# Power.net
KiCad netlist of a schematic drawn in Altium Designer
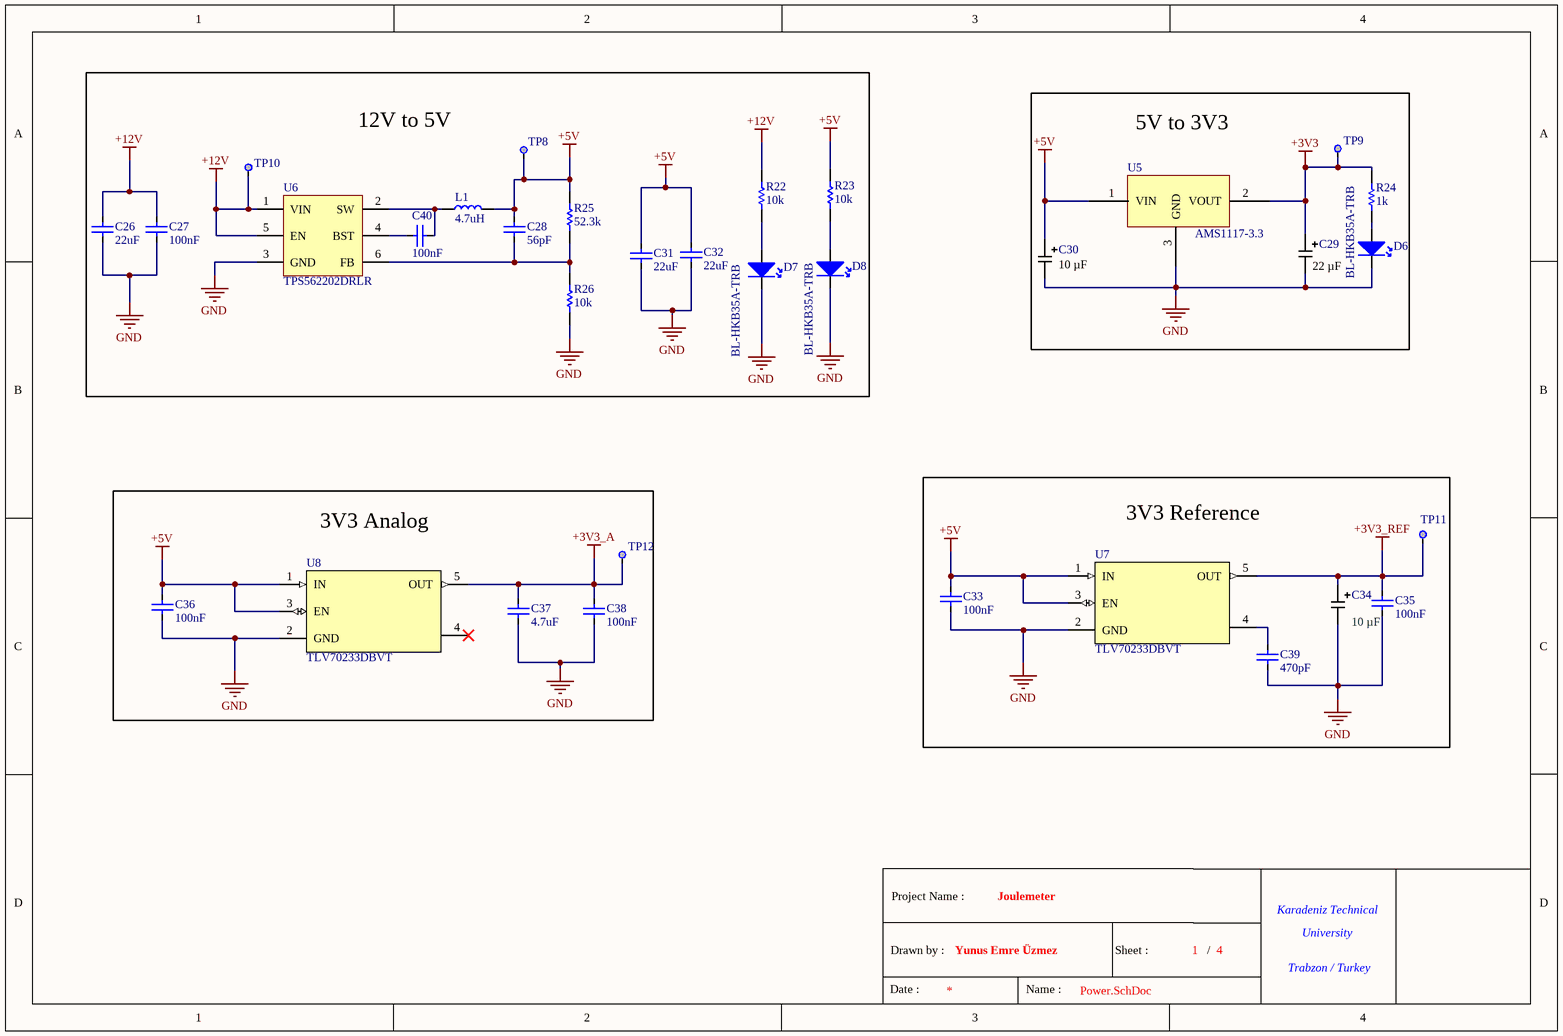
[diagram p0: Power.SchDoc]

(export (version "E")
  (design (tool "Eeschema 10.0.6"))
  (components
    (comp (ref "C26")
      (value "22uF")
      (footprint "CAP-1210")
      (fields
        (field (name "MANUFACTURER") "Samsung Electro-Mechanics")
        (field (name "VOLTAGE") "25V")
        (field (name "TOLERANCE") "%10")
      )
      (libsource (lib "Motor_Driver") (part "CL32B226KAJNNNE"))
    )
    (comp (ref "C27")
      (value "100nF")
      (footprint "CAP-0603")
      (fields
        (field (name "MANUFACTURER") "TDK")
        (field (name "VOLTAGE") "50V")
        (field (name "TOLERANCE") "%10")
      )
      (libsource (lib "Motor_Driver") (part "CGA3E2X7R1H104K080AA"))
    )
    (comp (ref "C28")
      (value "56pF")
      (footprint "Motor_Driver:CAP-0603")
      (fields
        (field (name "MANUFACTURER") "Murata")
        (field (name "TOLERANCE") "%1")
        (field (name "VOLTAGE") "100V")
      )
      (libsource (lib "My_Libs") (part "GCM1885C2A560FA16D"))
    )
    (comp (ref "C29")
      (value "T491B226K020AT")
      (footprint "KEMET_CAP_TAN-B")
      (description "CAP TANT 22UF 10% 20V 1411")
      (fields
        (field (name "MANUFACTURER") "KEMET")
        (field (name "TOLERANCE") "±10%")
        (field (name "CAPACITANCE") "22 µF")
      )
      (libsource (lib "Tantalum Capacitors") (part "T491B226K020AT"))
    )
    (comp (ref "C30")
      (value "T491B106M016AT")
      (footprint "KEMET_CAP_TAN-B")
      (description "CAP TANT 10UF 20% 16V 1411")
      (fields
        (field (name "MANUFACTURER") "KEMET")
        (field (name "TOLERANCE") "±20%")
        (field (name "CAPACITANCE") "10 µF")
      )
      (libsource (lib "Tantalum Capacitors") (part "T491B106M016AT"))
    )
    (comp (ref "C31")
      (value "22uF")
      (footprint "CAP-1210")
      (fields
        (field (name "MANUFACTURER") "Samsung Electro-Mechanics")
        (field (name "VOLTAGE") "25V")
        (field (name "TOLERANCE") "%10")
      )
      (libsource (lib "Motor_Driver") (part "CL32B226KAJNNNE"))
    )
    (comp (ref "C32")
      (value "22uF")
      (footprint "CAP-1210")
      (fields
        (field (name "MANUFACTURER") "Samsung Electro-Mechanics")
        (field (name "VOLTAGE") "25V")
        (field (name "TOLERANCE") "%10")
      )
      (libsource (lib "Motor_Driver") (part "CL32B226KAJNNNE"))
    )
    (comp (ref "C33")
      (value "100nF")
      (footprint "CAP-0603")
      (fields
        (field (name "MANUFACTURER") "TDK")
        (field (name "VOLTAGE") "50V")
        (field (name "TOLERANCE") "%10")
      )
      (libsource (lib "Motor_Driver") (part "CGA3E2X7R1H104K080AA"))
    )
    (comp (ref "C34")
      (value "T491B106M016AT")
      (footprint "KEMET_CAP_TAN-B")
      (description "CAP TANT 10UF 20% 16V 1411")
      (fields
        (field (name "MANUFACTURER") "KEMET")
        (field (name "TOLERANCE") "±20%")
        (field (name "CAPACITANCE") "10 µF")
      )
      (libsource (lib "Tantalum Capacitors") (part "T491B106M016AT"))
    )
    (comp (ref "C35")
      (value "100nF")
      (footprint "CAP-0603")
      (fields
        (field (name "MANUFACTURER") "TDK")
        (field (name "VOLTAGE") "50V")
        (field (name "TOLERANCE") "%10")
      )
      (libsource (lib "Motor_Driver") (part "CGA3E2X7R1H104K080AA"))
    )
    (comp (ref "C36")
      (value "100nF")
      (footprint "CAP-0603")
      (fields
        (field (name "MANUFACTURER") "TDK")
        (field (name "VOLTAGE") "50V")
        (field (name "TOLERANCE") "%10")
      )
      (libsource (lib "Motor_Driver") (part "CGA3E2X7R1H104K080AA"))
    )
    (comp (ref "C37")
      (value "4.7uF")
      (footprint "CAP-0805")
      (fields
        (field (name "MANUFACTURER") "Kemet")
        (field (name "VOLTAGE") "25V")
        (field (name "TOLERANCE") "%10")
      )
      (libsource (lib "Motor_Driver") (part "C0805C475K3RACAUTO"))
    )
    (comp (ref "C38")
      (value "100nF")
      (footprint "CAP-0603")
      (fields
        (field (name "MANUFACTURER") "TDK")
        (field (name "VOLTAGE") "50V")
        (field (name "TOLERANCE") "%10")
      )
      (libsource (lib "Motor_Driver") (part "CGA3E2X7R1H104K080AA"))
    )
    (comp (ref "C39")
      (value "470pF")
      (footprint "CAP-0603")
      (fields
        (field (name "VOLTAGE") "50V")
        (field (name "TOLERANCE") "%10")
        (field (name "MANUFACTURER") "Samsung")
      )
      (libsource (lib "jl_lib") (part "CL10B471KB8NNNC"))
    )
    (comp (ref "C40")
      (value "100nF")
      (footprint "Motor_Driver:CAP-0603")
      (fields
        (field (name "MANUFACTURER") "TDK")
        (field (name "VOLTAGE") "50V")
        (field (name "TOLERANCE") "%10")
      )
      (libsource (lib "My_Libs") (part "CGA3E2X7R1H104K080AA"))
    )
    (comp (ref "D6")
      (value "BL-HKB35A-TRB")
      (footprint "LED-0805")
      (fields (field (name "MANUFACTURER") "BRIGHT LED"))
      (libsource (lib "Motor_Driver") (part "BL-HKB35A-TRB"))
    )
    (comp (ref "D7")
      (value "BL-HKB35A-TRB")
      (footprint "LED-0805")
      (fields (field (name "MANUFACTURER") "BRIGHT LED"))
      (libsource (lib "Motor_Driver") (part "BL-HKB35A-TRB"))
    )
    (comp (ref "D8")
      (value "BL-HKB35A-TRB")
      (footprint "LED-0805")
      (fields (field (name "MANUFACTURER") "BRIGHT LED"))
      (libsource (lib "Motor_Driver") (part "BL-HKB35A-TRB"))
    )
    (comp (ref "L1")
      (value "4.7uH")
      (footprint "Motor_Driver:IND_EATON_DR125-4R7-R")
      (fields (field (name "MANUFACTURER") "Eaton") (field (name "TOLERANCE") "%20"))
      (libsource (lib "My_Libs") (part "DR125-4R7-R"))
    )
    (comp (ref "R22")
      (value "10k")
      (footprint "Motor_Driver:RES-0603")
      (fields
        (field (name "MANUFACTURER") "Vishay")
        (field (name "TOLERANCE") "%1")
        (field (name "POWER") "0.1W")
      )
      (libsource (lib "My_Libs") (part "CRCW060310K0FKEA"))
    )
    (comp (ref "R23")
      (value "10k")
      (footprint "Motor_Driver:RES-0603")
      (fields
        (field (name "MANUFACTURER") "Vishay")
        (field (name "TOLERANCE") "%1")
        (field (name "POWER") "0.1W")
      )
      (libsource (lib "My_Libs") (part "CRCW060310K0FKEA"))
    )
    (comp (ref "R24")
      (value "1k")
      (footprint "Motor_Driver:RES-0603")
      (fields
        (field (name "MANUFACTURER") "Vishay")
        (field (name "TOLERANCE") "%1")
        (field (name "POWER") "0.1W")
      )
      (libsource (lib "My_Libs") (part "CRCW06031K00FKEAC"))
    )
    (comp (ref "R25")
      (value "52.3k")
      (footprint "Motor_Driver:RES-0603")
      (fields
        (field (name "MANUFACTURER") "Panasonic")
        (field (name "TOLERANCE") "%1")
        (field (name "POWER") "0.1W")
      )
      (libsource (lib "My_Libs") (part "ERJ-3EKF5232V"))
    )
    (comp (ref "R26")
      (value "10k")
      (footprint "Motor_Driver:RES-0603")
      (fields
        (field (name "MANUFACTURER") "Vishay")
        (field (name "TOLERANCE") "%1")
        (field (name "POWER") "0.1W")
      )
      (libsource (lib "My_Libs") (part "CRCW060310K0FKEA"))
    )
    (comp (ref "TP8")
      (value "Test Point")
      (footprint "0.8mm Test Point")
      (libsource (lib "Motor_Driver") (part "Test Point"))
    )
    (comp (ref "TP9")
      (value "Test Point")
      (footprint "0.8mm Test Point")
      (libsource (lib "Motor_Driver") (part "Test Point"))
    )
    (comp (ref "TP10")
      (value "Test Point")
      (footprint "0.8mm Test Point")
      (libsource (lib "Motor_Driver") (part "Test Point"))
    )
    (comp (ref "TP11")
      (value "Test Point")
      (footprint "0.8mm Test Point")
      (libsource (lib "Motor_Driver") (part "Test Point"))
    )
    (comp (ref "TP12")
      (value "Test Point")
      (footprint "0.8mm Test Point")
      (libsource (lib "Motor_Driver") (part "Test Point"))
    )
    (comp (ref "U5")
      (value "AMS1117-3.3")
      (footprint "SOT-223")
      (fields (field (name "MANUFACTURER") "Monolithic"))
      (libsource (lib "jl_lib") (part "AMS1117-3.3"))
    )
    (comp (ref "U6")
      (value "TPS562202DRLR")
      (footprint "SOT-563")
      (fields (field (name "MANUFACTURER") "Texas Instruments"))
      (libsource (lib "Motor_Driver") (part "TPS562202DRLR"))
    )
    (comp (ref "U7")
      (value "TLV70233DBVT")
      (footprint "SOT23-5")
      (fields (field (name "MANUFACTURER") "TEXAS") (field (name "VOLTAGE") "3.3V"))
      (libsource (lib "jl_lib") (part "TLV70233DBVT"))
    )
    (comp (ref "U8")
      (value "TLV70233DBVT")
      (footprint "SOT23-5")
      (fields (field (name "MANUFACTURER") "TEXAS") (field (name "VOLTAGE") "3.3V"))
      (libsource (lib "jl_lib") (part "TLV70233DBVT"))
    )
  )
  (nets
    (net (code "1") (name "+3V3") (class "Default")
      (node (ref "C29") (pin "1") (pinfunction "1_1") (pintype "passive"))
      (node (ref "R24") (pin "1") (pinfunction "1_1") (pintype "passive"))
      (node (ref "TP9") (pin "1") (pinfunction "1_1") (pintype "passive"))
      (node (ref "U5") (pin "2") (pinfunction "VOUT_2") (pintype "passive"))
    )
    (net (code "2") (name "+3V3_A") (class "Default")
      (node (ref "C37") (pin "2") (pinfunction "2_2") (pintype "passive"))
      (node (ref "C38") (pin "2") (pinfunction "2_2") (pintype "passive"))
      (node (ref "TP12") (pin "1") (pinfunction "1_1") (pintype "passive"))
      (node (ref "U8") (pin "5") (pinfunction "OUT_5") (pintype "output"))
    )
    (net (code "3") (name "+3V3_REF") (class "Default")
      (node (ref "C34") (pin "1") (pinfunction "1_1") (pintype "passive"))
      (node (ref "C35") (pin "2") (pinfunction "2_2") (pintype "passive"))
      (node (ref "TP11") (pin "1") (pinfunction "1_1") (pintype "passive"))
      (node (ref "U7") (pin "5") (pinfunction "OUT_5") (pintype "output"))
    )
    (net (code "4") (name "+5V") (class "Default")
      (node (ref "C28") (pin "2") (pinfunction "2_2") (pintype "passive"))
      (node (ref "C30") (pin "1") (pinfunction "1_1") (pintype "passive"))
      (node (ref "C31") (pin "2") (pinfunction "2_2") (pintype "passive"))
      (node (ref "C32") (pin "2") (pinfunction "2_2") (pintype "passive"))
      (node (ref "C33") (pin "2") (pinfunction "2_2") (pintype "passive"))
      (node (ref "C36") (pin "2") (pinfunction "2_2") (pintype "passive"))
      (node (ref "L1") (pin "2") (pinfunction "2_2") (pintype "passive"))
      (node (ref "R23") (pin "2") (pinfunction "2_2") (pintype "passive"))
      (node (ref "R25") (pin "2") (pinfunction "2_2") (pintype "passive"))
      (node (ref "TP8") (pin "1") (pinfunction "1_1") (pintype "passive"))
      (node (ref "U5") (pin "1") (pinfunction "VIN_1") (pintype "passive"))
      (node (ref "U7") (pin "1") (pinfunction "IN_1") (pintype "input"))
      (node (ref "U7") (pin "3") (pinfunction "EN_3") (pintype "bidirectional"))
      (node (ref "U8") (pin "1") (pinfunction "IN_1") (pintype "input"))
      (node (ref "U8") (pin "3") (pinfunction "EN_3") (pintype "bidirectional"))
    )
    (net (code "5") (name "+12V") (class "Default")
      (node (ref "C26") (pin "2") (pinfunction "2_2") (pintype "passive"))
      (node (ref "C27") (pin "2") (pinfunction "2_2") (pintype "passive"))
      (node (ref "R22") (pin "2") (pinfunction "2_2") (pintype "passive"))
      (node (ref "TP10") (pin "1") (pinfunction "1_1") (pintype "passive"))
      (node (ref "U6") (pin "1") (pinfunction "VIN_1") (pintype "passive"))
      (node (ref "U6") (pin "5") (pinfunction "EN_5") (pintype "passive"))
    )
    (net (code "6") (name "GND") (class "Default")
      (node (ref "C26") (pin "1") (pinfunction "1_1") (pintype "passive"))
      (node (ref "C27") (pin "1") (pinfunction "1_1") (pintype "passive"))
      (node (ref "C29") (pin "2") (pinfunction "2_2") (pintype "passive"))
      (node (ref "C30") (pin "2") (pinfunction "2_2") (pintype "passive"))
      (node (ref "C31") (pin "1") (pinfunction "1_1") (pintype "passive"))
      (node (ref "C32") (pin "1") (pinfunction "1_1") (pintype "passive"))
      (node (ref "C33") (pin "1") (pinfunction "1_1") (pintype "passive"))
      (node (ref "C34") (pin "2") (pinfunction "2_2") (pintype "passive"))
      (node (ref "C35") (pin "1") (pinfunction "1_1") (pintype "passive"))
      (node (ref "C36") (pin "1") (pinfunction "1_1") (pintype "passive"))
      (node (ref "C37") (pin "1") (pinfunction "1_1") (pintype "passive"))
      (node (ref "C38") (pin "1") (pinfunction "1_1") (pintype "passive"))
      (node (ref "C39") (pin "1") (pinfunction "1_1") (pintype "passive"))
      (node (ref "D6") (pin "2") (pinfunction "K_2") (pintype "passive"))
      (node (ref "D7") (pin "2") (pinfunction "K_2") (pintype "passive"))
      (node (ref "D8") (pin "2") (pinfunction "K_2") (pintype "passive"))
      (node (ref "R26") (pin "1") (pinfunction "1_1") (pintype "passive"))
      (node (ref "U5") (pin "3") (pinfunction "GND_3") (pintype "passive"))
      (node (ref "U6") (pin "3") (pinfunction "GND_3") (pintype "passive"))
      (node (ref "U7") (pin "2") (pinfunction "GND_2") (pintype "power_in"))
      (node (ref "U8") (pin "2") (pinfunction "GND_2") (pintype "power_in"))
    )
    (net (code "7") (name "Net-(C39-Pad2)") (class "Default")
      (node (ref "C39") (pin "2") (pinfunction "2_2") (pintype "passive"))
      (node (ref "U7") (pin "4") (pintype "power_in"))
    )
    (net (code "8") (name "Net-(D6-A)") (class "Default")
      (node (ref "D6") (pin "1") (pinfunction "A_1") (pintype "passive"))
      (node (ref "R24") (pin "2") (pinfunction "2_2") (pintype "passive"))
    )
    (net (code "9") (name "Net-(D7-A)") (class "Default")
      (node (ref "D7") (pin "1") (pinfunction "A_1") (pintype "passive"))
      (node (ref "R22") (pin "1") (pinfunction "1_1") (pintype "passive"))
    )
    (net (code "10") (name "Net-(D8-A)") (class "Default")
      (node (ref "D8") (pin "1") (pinfunction "A_1") (pintype "passive"))
      (node (ref "R23") (pin "1") (pinfunction "1_1") (pintype "passive"))
    )
    (net (code "11") (name "Net-(U6-BST)") (class "Default")
      (node (ref "C40") (pin "2") (pinfunction "2_2") (pintype "passive"))
      (node (ref "U6") (pin "4") (pinfunction "BST_4") (pintype "passive"))
    )
    (net (code "12") (name "Net-(U6-FB)") (class "Default")
      (node (ref "C28") (pin "1") (pinfunction "1_1") (pintype "passive"))
      (node (ref "R25") (pin "1") (pinfunction "1_1") (pintype "passive"))
      (node (ref "R26") (pin "2") (pinfunction "2_2") (pintype "passive"))
      (node (ref "U6") (pin "6") (pinfunction "FB_6") (pintype "passive"))
    )
    (net (code "13") (name "Net-(U6-SW)") (class "Default")
      (node (ref "C40") (pin "1") (pinfunction "1_1") (pintype "passive"))
      (node (ref "L1") (pin "1") (pinfunction "1_1") (pintype "passive"))
      (node (ref "U6") (pin "2") (pinfunction "SW_2") (pintype "passive"))
    )
    (net (code "14") (name "unconnected-(U8-Pad4)") (class "Default")
      (node (ref "U8") (pin "4") (pintype "power_in+no_connect"))
    )
  )
)
